# Adaptor485mini.net
KiCad netlist of a schematic drawn in EAGLE
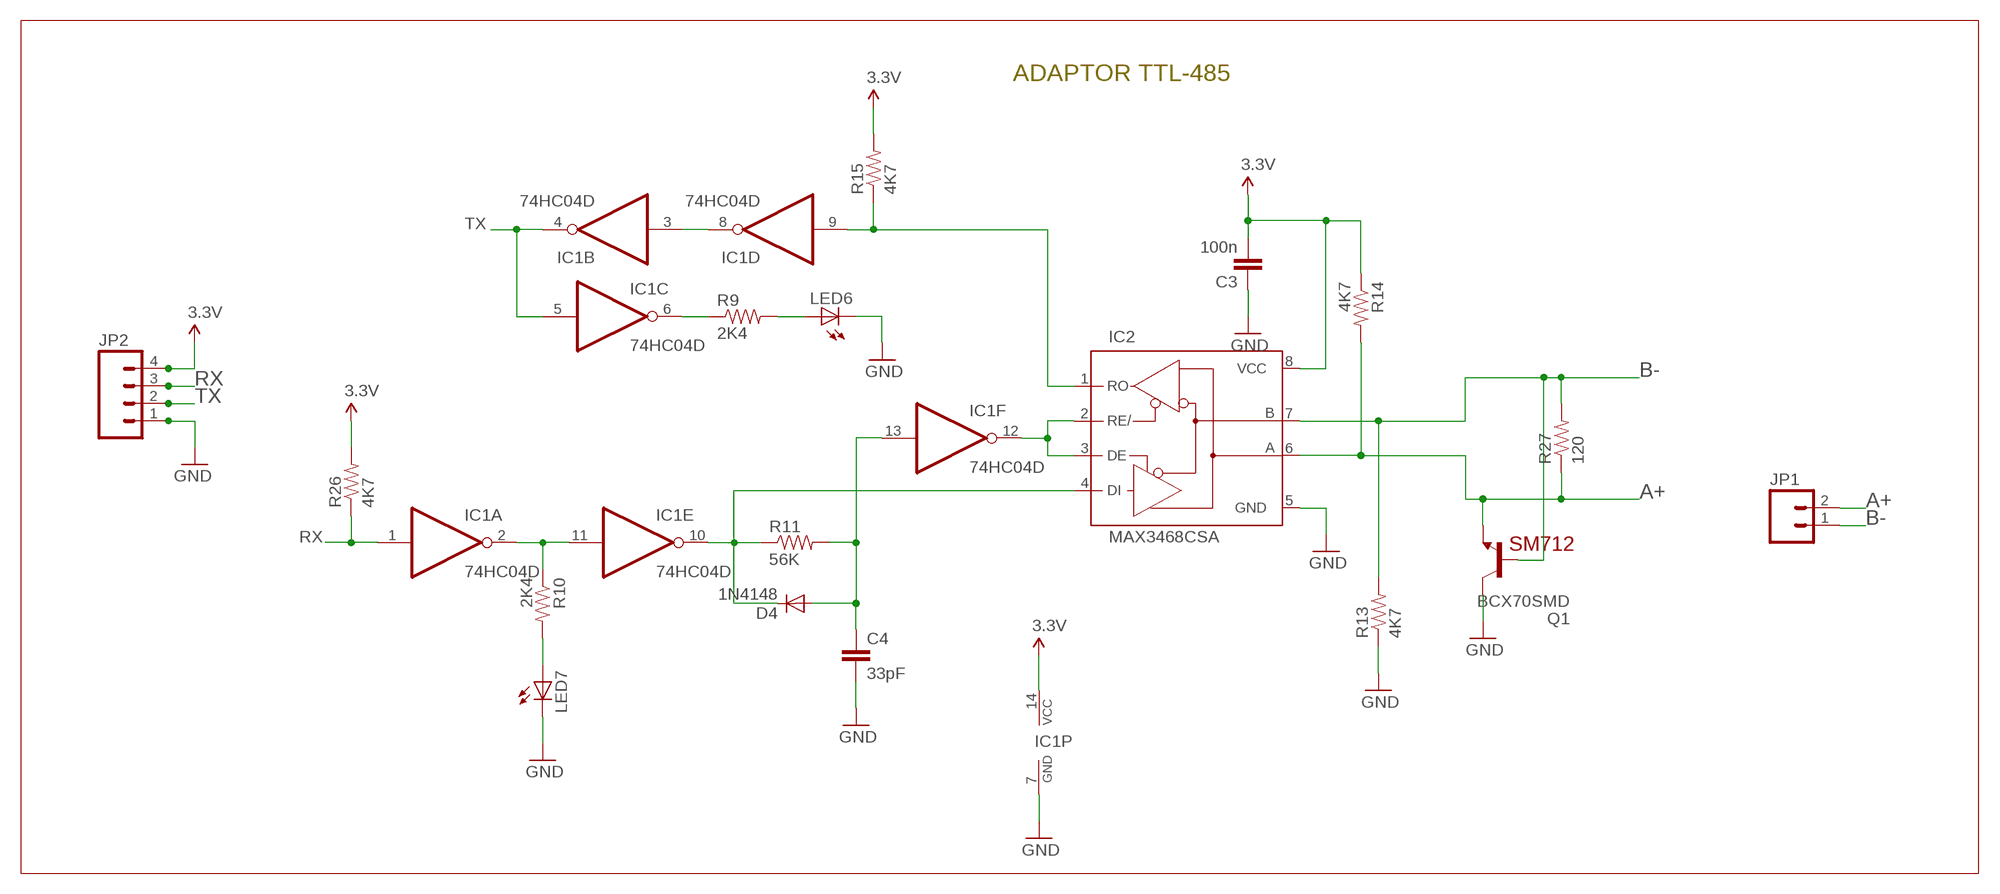
[diagram p0: schematic, sheet 1]

(export (version "E")
  (design (tool "Eeschema 10.0.6"))
  (components
    (comp (ref "C3")
      (value "100n")
      (footprint "eagle-import:0805")
      (libsource (lib "eagle-import") (part "CAP0805"))
    )
    (comp (ref "C4")
      (value "33pF")
      (footprint "eagle-import:0805")
      (libsource (lib "eagle-import") (part "CAP0805"))
    )
    (comp (ref "D4")
      (value "1N4148")
      (footprint "eagle-import:MINIMELF")
      (libsource (lib "eagle-import") (part "DIODE-MINIMELF"))
    )
    (comp (ref "IC1")
      (value "74HC04D")
      (footprint "eagle-import:SO14")
      (libsource (lib "eagle-import") (part "7404DHC"))
    )
    (comp (ref "IC2")
      (value "MAX3468CSA")
      (footprint "eagle-import:SO08")
      (fields (field (name "MPN") "MAX3468CSA+"))
      (libsource (lib "eagle-import") (part "MAX34SA68C"))
    )
    (comp (ref "JP1")
      (value "M02PTH")
      (footprint "eagle-import:1X02")
      (libsource (lib "eagle-import") (part "M02PTH"))
    )
    (comp (ref "JP2")
      (value "M04PTH")
      (footprint "eagle-import:1X04")
      (libsource (lib "eagle-import") (part "M04PTH"))
    )
    (comp (ref "LED6")
      (value "LEDCHIP-LED0805")
      (footprint "eagle-import:CHIP-LED0805")
      (libsource (lib "eagle-import") (part "LEDCHIP-LED0805"))
    )
    (comp (ref "LED7")
      (value "LEDCHIP-LED0805")
      (footprint "eagle-import:CHIP-LED0805")
      (libsource (lib "eagle-import") (part "LEDCHIP-LED0805"))
    )
    (comp (ref "Q1")
      (value "BCX70SMD")
      (footprint "eagle-import:SOT23")
      (libsource (lib "eagle-import") (part "BCX70SMD"))
    )
    (comp (ref "R9")
      (value "2K4")
      (footprint "eagle-import:0805")
      (libsource (lib "eagle-import") (part "RESISTOR0805-RES"))
    )
    (comp (ref "R10")
      (value "2K4")
      (footprint "eagle-import:0805")
      (libsource (lib "eagle-import") (part "RESISTOR0805-RES"))
    )
    (comp (ref "R11")
      (value "56K")
      (footprint "eagle-import:0805")
      (libsource (lib "eagle-import") (part "RESISTOR0805-RES"))
    )
    (comp (ref "R13")
      (value "4K7")
      (footprint "eagle-import:0805")
      (libsource (lib "eagle-import") (part "RESISTOR0805-RES"))
    )
    (comp (ref "R14")
      (value "4K7")
      (footprint "eagle-import:0805")
      (libsource (lib "eagle-import") (part "RESISTOR0805-RES"))
    )
    (comp (ref "R15")
      (value "4K7")
      (footprint "eagle-import:0805")
      (libsource (lib "eagle-import") (part "RESISTOR0805-RES"))
    )
    (comp (ref "R26")
      (value "4K7")
      (footprint "eagle-import:0805")
      (libsource (lib "eagle-import") (part "RESISTOR0805-RES"))
    )
    (comp (ref "R27")
      (value "120")
      (footprint "eagle-import:0805")
      (libsource (lib "eagle-import") (part "RESISTOR0805-RES"))
    )
  )
  (nets
    (net (code "1") (name "/A+") (class "Default")
      (node (ref "IC2") (pin "6") (pinfunction "A_6") (pintype "passive"))
      (node (ref "JP1") (pin "2") (pinfunction "2_2") (pintype "passive"))
      (node (ref "Q1") (pin "2") (pinfunction "E_2") (pintype "passive"))
      (node (ref "R14") (pin "2") (pinfunction "2_2") (pintype "passive"))
      (node (ref "R27") (pin "1") (pinfunction "1_1") (pintype "passive"))
    )
    (net (code "2") (name "/B-") (class "Default")
      (node (ref "IC2") (pin "7") (pinfunction "B_7") (pintype "passive"))
      (node (ref "JP1") (pin "1") (pinfunction "1_1") (pintype "passive"))
      (node (ref "Q1") (pin "1") (pinfunction "B_1") (pintype "passive"))
      (node (ref "R13") (pin "2") (pinfunction "2_2") (pintype "passive"))
      (node (ref "R27") (pin "2") (pinfunction "2_2") (pintype "passive"))
    )
    (net (code "3") (name "/RX") (class "Default")
      (node (ref "IC1") (pin "1") (pinfunction "I_1") (pintype "input"))
      (node (ref "JP2") (pin "3") (pinfunction "3_3") (pintype "passive"))
      (node (ref "R26") (pin "1") (pinfunction "1_1") (pintype "passive"))
    )
    (net (code "4") (name "/TX") (class "Default")
      (node (ref "IC1") (pin "4") (pinfunction "O_4") (pintype "output"))
      (node (ref "IC1") (pin "5") (pinfunction "I_5") (pintype "input"))
      (node (ref "JP2") (pin "2") (pinfunction "2_2") (pintype "passive"))
    )
    (net (code "5") (name "3.3V") (class "Default")
      (node (ref "C3") (pin "2") (pinfunction "2_2") (pintype "passive"))
      (node (ref "IC1") (pin "14") (pinfunction "VCC_14") (pintype "power_in"))
      (node (ref "IC2") (pin "8") (pinfunction "VCC_8") (pintype "power_in"))
      (node (ref "JP2") (pin "4") (pinfunction "4_4") (pintype "passive"))
      (node (ref "R14") (pin "1") (pinfunction "1_1") (pintype "passive"))
      (node (ref "R15") (pin "2") (pinfunction "2_2") (pintype "passive"))
      (node (ref "R26") (pin "2") (pinfunction "2_2") (pintype "passive"))
    )
    (net (code "6") (name "GND") (class "Default")
      (node (ref "C3") (pin "1") (pinfunction "1_1") (pintype "passive"))
      (node (ref "C4") (pin "2") (pinfunction "2_2") (pintype "passive"))
      (node (ref "IC1") (pin "7") (pinfunction "GND_7") (pintype "power_in"))
      (node (ref "IC2") (pin "5") (pinfunction "GND_5") (pintype "power_in"))
      (node (ref "JP2") (pin "1") (pinfunction "1_1") (pintype "passive"))
      (node (ref "LED6") (pin "C") (pinfunction "C_C") (pintype "passive"))
      (node (ref "LED7") (pin "C") (pinfunction "C_C") (pintype "passive"))
      (node (ref "Q1") (pin "3") (pinfunction "C_3") (pintype "passive"))
      (node (ref "R13") (pin "1") (pinfunction "1_1") (pintype "passive"))
    )
    (net (code "7") (name "Net-(IC1A-O)") (class "Default")
      (node (ref "IC1") (pin "11") (pinfunction "I_11") (pintype "input"))
      (node (ref "IC1") (pin "2") (pinfunction "O_2") (pintype "output"))
      (node (ref "R10") (pin "1") (pinfunction "1_1") (pintype "passive"))
    )
    (net (code "8") (name "Net-(IC1B-I)") (class "Default")
      (node (ref "IC1") (pin "3") (pinfunction "I_3") (pintype "input"))
      (node (ref "IC1") (pin "8") (pinfunction "O_8") (pintype "output"))
    )
    (net (code "9") (name "Net-(IC1C-O)") (class "Default")
      (node (ref "IC1") (pin "6") (pinfunction "O_6") (pintype "output"))
      (node (ref "R9") (pin "1") (pinfunction "1_1") (pintype "passive"))
    )
    (net (code "10") (name "Net-(IC1D-I)") (class "Default")
      (node (ref "IC1") (pin "9") (pinfunction "I_9") (pintype "input"))
      (node (ref "IC2") (pin "1") (pinfunction "RO_1") (pintype "output"))
      (node (ref "R15") (pin "1") (pinfunction "1_1") (pintype "passive"))
    )
    (net (code "11") (name "Net-(IC1E-O)") (class "Default")
      (node (ref "D4") (pin "C") (pinfunction "C_C") (pintype "passive"))
      (node (ref "IC1") (pin "10") (pinfunction "O_10") (pintype "output"))
      (node (ref "IC2") (pin "4") (pinfunction "DI_4") (pintype "input"))
      (node (ref "R11") (pin "1") (pinfunction "1_1") (pintype "passive"))
    )
    (net (code "12") (name "Net-(IC1F-I)") (class "Default")
      (node (ref "C4") (pin "1") (pinfunction "1_1") (pintype "passive"))
      (node (ref "D4") (pin "A") (pinfunction "A_A") (pintype "passive"))
      (node (ref "IC1") (pin "13") (pinfunction "I_13") (pintype "input"))
      (node (ref "R11") (pin "2") (pinfunction "2_2") (pintype "passive"))
    )
    (net (code "13") (name "Net-(IC1F-O)") (class "Default")
      (node (ref "IC1") (pin "12") (pinfunction "O_12") (pintype "output"))
      (node (ref "IC2") (pin "2") (pinfunction "RE/_2") (pintype "input"))
      (node (ref "IC2") (pin "3") (pinfunction "DE_3") (pintype "input"))
    )
    (net (code "14") (name "Net-(LED6-PadA)") (class "Default")
      (node (ref "LED6") (pin "A") (pinfunction "A_A") (pintype "passive"))
      (node (ref "R9") (pin "2") (pinfunction "2_2") (pintype "passive"))
    )
    (net (code "15") (name "Net-(LED7-PadA)") (class "Default")
      (node (ref "LED7") (pin "A") (pinfunction "A_A") (pintype "passive"))
      (node (ref "R10") (pin "2") (pinfunction "2_2") (pintype "passive"))
    )
  )
)
